# pwrsupply1.net
KiCad netlist of a schematic drawn in EAGLE
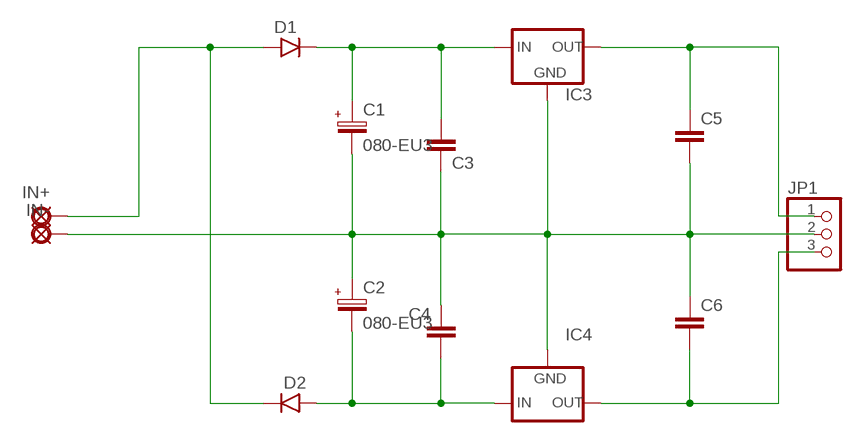
[diagram p0: schematic, sheet 1]

(export (version "E")
  (design (tool "Eeschema 10.0.6"))
  (components
    (comp (ref "C1")
      (value "080-EU3")
      (footprint "eagle-import:080_035_3")
      (libsource (lib "eagle-import") (part "080-EU3"))
    )
    (comp (ref "C2")
      (value "080-EU3")
      (footprint "eagle-import:080_035_3")
      (libsource (lib "eagle-import") (part "080-EU3"))
    )
    (comp (ref "C3")
      (value "070X0303")
      (footprint "eagle-import:070X030_3")
      (libsource (lib "eagle-import") (part "070X0303"))
    )
    (comp (ref "C4")
      (value "070X0303")
      (footprint "eagle-import:070X030_3")
      (libsource (lib "eagle-import") (part "070X0303"))
    )
    (comp (ref "C5")
      (value "070X0305")
      (footprint "eagle-import:070X030_5")
      (libsource (lib "eagle-import") (part "070X0305"))
    )
    (comp (ref "C6")
      (value "070X0302")
      (footprint "eagle-import:070X030")
      (libsource (lib "eagle-import") (part "070X0302"))
    )
    (comp (ref "D1")
      (value "1N400X.4")
      (footprint "eagle-import:DO41-4")
      (libsource (lib "eagle-import") (part "1N400X.4"))
    )
    (comp (ref "D2")
      (value "1N400X.4")
      (footprint "eagle-import:DO41-4")
      (libsource (lib "eagle-import") (part "1N400X.4"))
    )
    (comp (ref "IC3")
      (value "78XXL")
      (footprint "eagle-import:78XXL")
      (libsource (lib "eagle-import") (part "78XXL"))
    )
    (comp (ref "IC4")
      (value "79XXL")
      (footprint "eagle-import:79XXL")
      (libsource (lib "eagle-import") (part "79XXL"))
    )
    (comp (ref "IN+")
      (value "PAD8")
      (footprint "eagle-import:OCTOGON")
      (libsource (lib "eagle-import") (part "PAD8"))
    )
    (comp (ref "IN-")
      (value "PAD8")
      (footprint "eagle-import:OCTOGON")
      (libsource (lib "eagle-import") (part "PAD8"))
    )
    (comp (ref "JP1")
      (value "PINHD-1X3")
      (footprint "eagle-import:1X03")
      (libsource (lib "eagle-import") (part "PINHD-1X3"))
    )
  )
  (nets
    (net (code "1") (name "Net-(C1-Pad+)") (class "Default")
      (node (ref "C1") (pin "+") (pinfunction "+_+") (pintype "passive"))
      (node (ref "C3") (pin "2") (pinfunction "2_2") (pintype "passive"))
      (node (ref "D1") (pin "C") (pinfunction "C_C") (pintype "passive"))
      (node (ref "IC3") (pin "IN") (pinfunction "IN_IN") (pintype "input"))
    )
    (net (code "2") (name "Net-(C2-Pad-)") (class "Default")
      (node (ref "C2") (pin "-") (pinfunction "-_-") (pintype "passive"))
      (node (ref "C4") (pin "2") (pinfunction "2_2") (pintype "passive"))
      (node (ref "D2") (pin "A") (pinfunction "A_A") (pintype "passive"))
      (node (ref "IC4") (pin "IN") (pinfunction "IN_IN") (pintype "input"))
    )
    (net (code "3") (name "Net-(C5-Pad1)") (class "Default")
      (node (ref "C5") (pin "1") (pinfunction "1_1") (pintype "passive"))
      (node (ref "IC3") (pin "OUT") (pinfunction "OUT_OUT") (pintype "passive"))
      (node (ref "JP1") (pin "1") (pinfunction "1_1") (pintype "passive"))
    )
    (net (code "4") (name "Net-(C6-Pad2)") (class "Default")
      (node (ref "C6") (pin "2") (pinfunction "2_2") (pintype "passive"))
      (node (ref "IC4") (pin "OUT") (pinfunction "OUT_OUT") (pintype "passive"))
      (node (ref "JP1") (pin "3") (pinfunction "3_3") (pintype "passive"))
    )
    (net (code "5") (name "Net-(IN+-PAD)") (class "Default")
      (node (ref "D1") (pin "A") (pinfunction "A_A") (pintype "passive"))
      (node (ref "D2") (pin "C") (pinfunction "C_C") (pintype "passive"))
      (node (ref "IN+") (pin "1") (pinfunction "PAD_1") (pintype "passive"))
    )
    (net (code "6") (name "Net-(IN--PAD)") (class "Default")
      (node (ref "C1") (pin "-") (pinfunction "-_-") (pintype "passive"))
      (node (ref "C2") (pin "+") (pinfunction "+_+") (pintype "passive"))
      (node (ref "C3") (pin "1") (pinfunction "1_1") (pintype "passive"))
      (node (ref "C4") (pin "1") (pinfunction "1_1") (pintype "passive"))
      (node (ref "C5") (pin "2") (pinfunction "2_2") (pintype "passive"))
      (node (ref "C6") (pin "1") (pinfunction "1_1") (pintype "passive"))
      (node (ref "IC3") (pin "GND") (pinfunction "GND_GND") (pintype "input"))
      (node (ref "IC4") (pin "GND") (pinfunction "GND_GND") (pintype "input"))
      (node (ref "IN-") (pin "1") (pinfunction "PAD_1") (pintype "passive"))
      (node (ref "JP1") (pin "2") (pinfunction "2_2") (pintype "passive"))
    )
  )
)
